# TC-ADAPT.net
KiCad netlist of a schematic drawn in Altium Designer
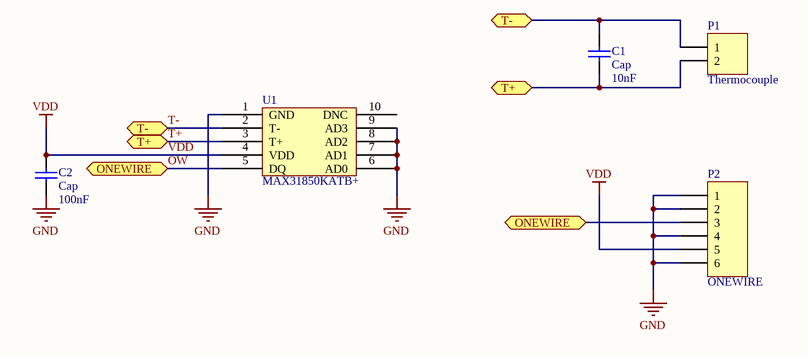
[diagram p0: TC-ADAPT.SchDoc]

(export (version "E")
  (design (tool "Eeschema 10.0.6"))
  (components
    (comp (ref "C1")
      (value "Cap")
      (footprint "0603")
      (description "Capacitor")
      (fields (field (name "ALTIUM_VALUE") "10nF"))
      (libsource (lib "Miscellaneous Devices") (part "Cap"))
    )
    (comp (ref "C2")
      (value "Cap")
      (footprint "0603")
      (description "Capacitor")
      (fields (field (name "ALTIUM_VALUE") "100nF"))
      (libsource (lib "Miscellaneous Devices") (part "Cap"))
    )
    (comp (ref "P1")
      (value "Thermocouple")
      (footprint "PCC-SMP")
      (description "Header, 2-Pin")
      (fields (field (name "PUBLISHER") "Altium Limited"))
      (libsource (lib "Miscellaneous Connectors") (part "Header 2"))
    )
    (comp (ref "P2")
      (value "ONEWIRE")
      (footprint "CONN MOD JACK R/A 6P6C")
      (description "Header, 6-Pin")
      (libsource (lib "Miscellaneous Connectors") (part "Header 6"))
    )
    (comp (ref "U1")
      (value "MAX31850KATB+")
      (footprint "TDFN-EP - MAX31850")
      (libsource (lib "BrewBit") (part "MAX31850KATB+"))
    )
  )
  (nets
    (net (code "1") (name "/OW") (class "Default")
      (node (ref "P2") (pin "3") (pinfunction "3_3") (pintype "passive"))
      (node (ref "U1") (pin "5") (pinfunction "DQ_5") (pintype "passive"))
    )
    (net (code "2") (name "/T+") (class "Default")
      (node (ref "C1") (pin "2") (pinfunction "2_2") (pintype "passive"))
      (node (ref "P1") (pin "2") (pinfunction "2_2") (pintype "passive"))
      (node (ref "U1") (pin "3") (pinfunction "T+_3") (pintype "passive"))
    )
    (net (code "3") (name "/T-") (class "Default")
      (node (ref "C1") (pin "1") (pinfunction "1_1") (pintype "passive"))
      (node (ref "P1") (pin "1") (pinfunction "1_1") (pintype "passive"))
      (node (ref "U1") (pin "2") (pinfunction "T-_2") (pintype "passive"))
    )
    (net (code "4") (name "GND") (class "Default")
      (node (ref "C2") (pin "2") (pinfunction "2_2") (pintype "passive"))
      (node (ref "P2") (pin "1") (pinfunction "1_1") (pintype "passive"))
      (node (ref "P2") (pin "2") (pinfunction "2_2") (pintype "passive"))
      (node (ref "P2") (pin "4") (pinfunction "4_4") (pintype "passive"))
      (node (ref "P2") (pin "6") (pinfunction "6_6") (pintype "passive"))
      (node (ref "U1") (pin "1") (pinfunction "GND_1") (pintype "passive"))
      (node (ref "U1") (pin "6") (pinfunction "AD0_6") (pintype "passive"))
      (node (ref "U1") (pin "7") (pinfunction "AD1_7") (pintype "passive"))
      (node (ref "U1") (pin "8") (pinfunction "AD2_8") (pintype "passive"))
      (node (ref "U1") (pin "9") (pinfunction "AD3_9") (pintype "passive"))
    )
    (net (code "5") (name "VDD") (class "Default")
      (node (ref "C2") (pin "1") (pinfunction "1_1") (pintype "passive"))
      (node (ref "P2") (pin "5") (pinfunction "5_5") (pintype "passive"))
      (node (ref "U1") (pin "4") (pinfunction "VDD_4") (pintype "passive"))
    )
    (net (code "6") (name "unconnected-(U1-DNC-Pad10)") (class "Default")
      (node (ref "U1") (pin "10") (pinfunction "DNC_10") (pintype "passive"))
    )
  )
)
